# CumLED.net
KiCad netlist of a schematic drawn in Altium Designer
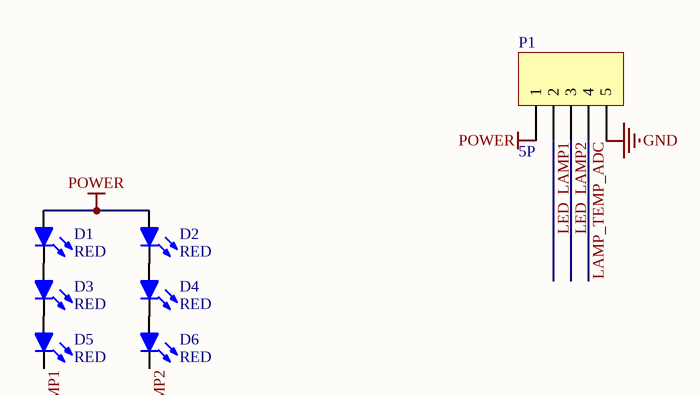
[diagram p0: CumLED.SchDoc]

(export (version "E")
  (design (tool "Eeschema 10.0.6"))
  (components
    (comp (ref "D1")
      (value "RED")
      (footprint "led_luxeon")
      (description "Typical INFRARED GaAs LED")
      (fields (field (name "Comment") "LED dán 0805RED") (field (name "PUBLISHER") "*"))
      (libsource (lib "DnsSchLib") (part "LED0"))
    )
    (comp (ref "D2")
      (value "RED")
      (footprint "led_luxeon")
      (description "Typical INFRARED GaAs LED")
      (fields (field (name "Comment") "LED dán 0805RED") (field (name "PUBLISHER") "*"))
      (libsource (lib "DnsSchLib") (part "LED0"))
    )
    (comp (ref "D3")
      (value "RED")
      (footprint "led_luxeon")
      (description "Typical INFRARED GaAs LED")
      (fields (field (name "Comment") "LED dán 0805RED") (field (name "PUBLISHER") "*"))
      (libsource (lib "DnsSchLib") (part "LED0"))
    )
    (comp (ref "D4")
      (value "RED")
      (footprint "led_luxeon")
      (description "Typical INFRARED GaAs LED")
      (fields (field (name "Comment") "LED dán 0805RED") (field (name "PUBLISHER") "*"))
      (libsource (lib "DnsSchLib") (part "LED0"))
    )
    (comp (ref "D5")
      (value "RED")
      (footprint "led_luxeon")
      (description "Typical INFRARED GaAs LED")
      (fields (field (name "Comment") "LED dán 0805RED") (field (name "PUBLISHER") "*"))
      (libsource (lib "DnsSchLib") (part "LED0"))
    )
    (comp (ref "D6")
      (value "RED")
      (footprint "led_luxeon")
      (description "Typical INFRARED GaAs LED")
      (fields (field (name "Comment") "LED dán 0805RED") (field (name "PUBLISHER") "*"))
      (libsource (lib "DnsSchLib") (part "LED0"))
    )
    (comp (ref "P1")
      (value "5P")
      (footprint "HDR1X5H")
      (description "Header, 5-Pin, Right Angle")
      (fields
        (field (name "Comment") "Jump đực chân thẳng, 2.54mm 5P")
        (field (name "PUBLISHER") "Altium Limited")
      )
      (libsource (lib "Miscellaneous Connectors") (part "Header 5H"))
    )
  )
  (nets
    (net (code "1") (name "/LAMP_TEMP_ADC") (class "Default")
      (node (ref "P1") (pin "4") (pinfunction "4_4") (pintype "passive"))
    )
    (net (code "2") (name "/LED_LAMP1") (class "Default")
      (node (ref "D5") (pin "2") (pinfunction "K_2") (pintype "passive"))
      (node (ref "P1") (pin "2") (pinfunction "2_2") (pintype "passive"))
    )
    (net (code "3") (name "/LED_LAMP2") (class "Default")
      (node (ref "D6") (pin "2") (pinfunction "K_2") (pintype "passive"))
      (node (ref "P1") (pin "3") (pinfunction "3_3") (pintype "passive"))
    )
    (net (code "4") (name "GND") (class "Default")
      (node (ref "P1") (pin "5") (pinfunction "5_5") (pintype "passive"))
    )
    (net (code "5") (name "Net-(D1-K)") (class "Default")
      (node (ref "D1") (pin "2") (pinfunction "K_2") (pintype "passive"))
      (node (ref "D3") (pin "1") (pinfunction "A_1") (pintype "passive"))
    )
    (net (code "6") (name "Net-(D2-K)") (class "Default")
      (node (ref "D2") (pin "2") (pinfunction "K_2") (pintype "passive"))
      (node (ref "D4") (pin "1") (pinfunction "A_1") (pintype "passive"))
    )
    (net (code "7") (name "Net-(D3-K)") (class "Default")
      (node (ref "D3") (pin "2") (pinfunction "K_2") (pintype "passive"))
      (node (ref "D5") (pin "1") (pinfunction "A_1") (pintype "passive"))
    )
    (net (code "8") (name "Net-(D4-K)") (class "Default")
      (node (ref "D4") (pin "2") (pinfunction "K_2") (pintype "passive"))
      (node (ref "D6") (pin "1") (pinfunction "A_1") (pintype "passive"))
    )
    (net (code "9") (name "POWER") (class "Default")
      (node (ref "D1") (pin "1") (pinfunction "A_1") (pintype "passive"))
      (node (ref "D2") (pin "1") (pinfunction "A_1") (pintype "passive"))
      (node (ref "P1") (pin "1") (pinfunction "1_1") (pintype "passive"))
    )
  )
)
